# eksos-rj45-breakout16.net
KiCad netlist of a schematic drawn in EAGLE
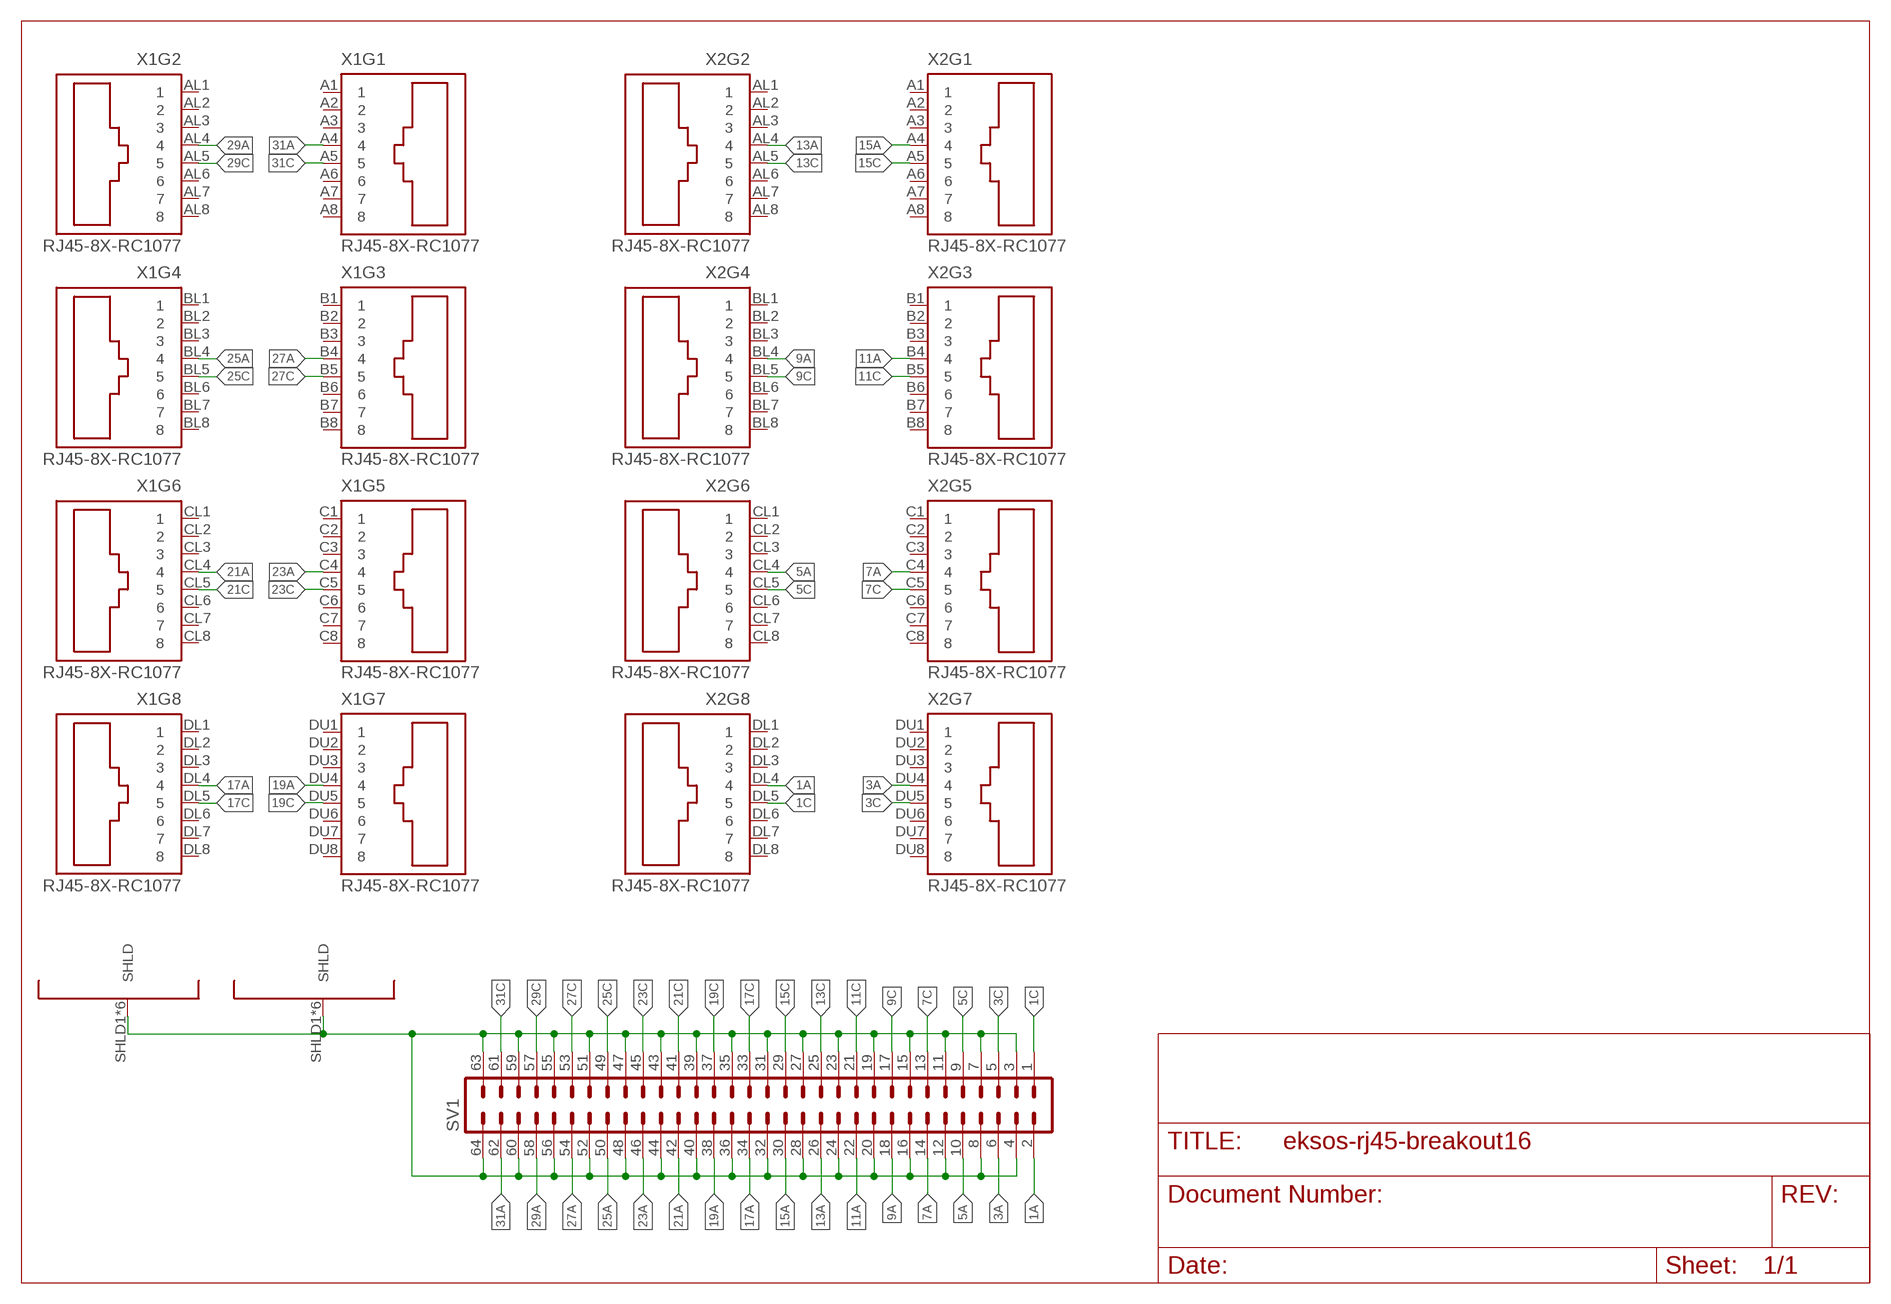
[diagram p0: schematic, sheet 1]

(export (version "E")
  (design (tool "Eeschema 10.0.6"))
  (components
    (comp (ref "SV1")
      (value "ML64")
      (footprint "eagle-import:ML64")
      (libsource (lib "eagle-import") (part "ML64"))
    )
    (comp (ref "X1")
      (value "RJ45-8X-RC1077")
      (footprint "eagle-import:RC01077")
      (libsource (lib "eagle-import") (part "RJ45-8X-RC1077"))
    )
    (comp (ref "X2")
      (value "RJ45-8X-RC1077")
      (footprint "eagle-import:RC01077")
      (libsource (lib "eagle-import") (part "RJ45-8X-RC1077"))
    )
  )
  (nets
    (net (code "1") (name "1A") (class "Default")
      (node (ref "SV1") (pin "2") (pinfunction "2_2") (pintype "passive"))
      (node (ref "X2") (pin "DL4") (pinfunction "4_DL4") (pintype "passive"))
    )
    (net (code "2") (name "1C") (class "Default")
      (node (ref "SV1") (pin "1") (pinfunction "1_1") (pintype "passive"))
      (node (ref "X2") (pin "DL5") (pinfunction "5_DL5") (pintype "passive"))
    )
    (net (code "3") (name "3A") (class "Default")
      (node (ref "SV1") (pin "6") (pinfunction "6_6") (pintype "passive"))
      (node (ref "X2") (pin "DU4") (pinfunction "4_DU4") (pintype "passive"))
    )
    (net (code "4") (name "3C") (class "Default")
      (node (ref "SV1") (pin "5") (pinfunction "5_5") (pintype "passive"))
      (node (ref "X2") (pin "DU5") (pinfunction "5_DU5") (pintype "passive"))
    )
    (net (code "5") (name "5A") (class "Default")
      (node (ref "SV1") (pin "10") (pinfunction "10_10") (pintype "passive"))
      (node (ref "X2") (pin "CL4") (pinfunction "4_CL4") (pintype "passive"))
    )
    (net (code "6") (name "5C") (class "Default")
      (node (ref "SV1") (pin "9") (pinfunction "9_9") (pintype "passive"))
      (node (ref "X2") (pin "CL5") (pinfunction "5_CL5") (pintype "passive"))
    )
    (net (code "7") (name "7A") (class "Default")
      (node (ref "SV1") (pin "14") (pinfunction "14_14") (pintype "passive"))
      (node (ref "X2") (pin "C4") (pinfunction "4_C4") (pintype "passive"))
    )
    (net (code "8") (name "7C") (class "Default")
      (node (ref "SV1") (pin "13") (pinfunction "13_13") (pintype "passive"))
      (node (ref "X2") (pin "C5") (pinfunction "5_C5") (pintype "passive"))
    )
    (net (code "9") (name "9A") (class "Default")
      (node (ref "SV1") (pin "18") (pinfunction "18_18") (pintype "passive"))
      (node (ref "X2") (pin "BL4") (pinfunction "4_BL4") (pintype "passive"))
    )
    (net (code "10") (name "9C") (class "Default")
      (node (ref "SV1") (pin "17") (pinfunction "17_17") (pintype "passive"))
      (node (ref "X2") (pin "BL5") (pinfunction "5_BL5") (pintype "passive"))
    )
    (net (code "11") (name "11A") (class "Default")
      (node (ref "SV1") (pin "22") (pinfunction "22_22") (pintype "passive"))
      (node (ref "X2") (pin "B4") (pinfunction "4_B4") (pintype "passive"))
    )
    (net (code "12") (name "11C") (class "Default")
      (node (ref "SV1") (pin "21") (pinfunction "21_21") (pintype "passive"))
      (node (ref "X2") (pin "B5") (pinfunction "5_B5") (pintype "passive"))
    )
    (net (code "13") (name "13A") (class "Default")
      (node (ref "SV1") (pin "26") (pinfunction "26_26") (pintype "passive"))
      (node (ref "X2") (pin "AL4") (pinfunction "4_AL4") (pintype "passive"))
    )
    (net (code "14") (name "13C") (class "Default")
      (node (ref "SV1") (pin "25") (pinfunction "25_25") (pintype "passive"))
      (node (ref "X2") (pin "AL5") (pinfunction "5_AL5") (pintype "passive"))
    )
    (net (code "15") (name "15A") (class "Default")
      (node (ref "SV1") (pin "30") (pinfunction "30_30") (pintype "passive"))
      (node (ref "X2") (pin "A4") (pinfunction "4_A4") (pintype "passive"))
    )
    (net (code "16") (name "15C") (class "Default")
      (node (ref "SV1") (pin "29") (pinfunction "29_29") (pintype "passive"))
      (node (ref "X2") (pin "A5") (pinfunction "5_A5") (pintype "passive"))
    )
    (net (code "17") (name "17A") (class "Default")
      (node (ref "SV1") (pin "34") (pinfunction "34_34") (pintype "passive"))
      (node (ref "X1") (pin "DL4") (pinfunction "4_DL4") (pintype "passive"))
    )
    (net (code "18") (name "17C") (class "Default")
      (node (ref "SV1") (pin "33") (pinfunction "33_33") (pintype "passive"))
      (node (ref "X1") (pin "DL5") (pinfunction "5_DL5") (pintype "passive"))
    )
    (net (code "19") (name "19A") (class "Default")
      (node (ref "SV1") (pin "38") (pinfunction "38_38") (pintype "passive"))
      (node (ref "X1") (pin "DU4") (pinfunction "4_DU4") (pintype "passive"))
    )
    (net (code "20") (name "19C") (class "Default")
      (node (ref "SV1") (pin "37") (pinfunction "37_37") (pintype "passive"))
      (node (ref "X1") (pin "DU5") (pinfunction "5_DU5") (pintype "passive"))
    )
    (net (code "21") (name "21A") (class "Default")
      (node (ref "SV1") (pin "42") (pinfunction "42_42") (pintype "passive"))
      (node (ref "X1") (pin "CL4") (pinfunction "4_CL4") (pintype "passive"))
    )
    (net (code "22") (name "21C") (class "Default")
      (node (ref "SV1") (pin "41") (pinfunction "41_41") (pintype "passive"))
      (node (ref "X1") (pin "CL5") (pinfunction "5_CL5") (pintype "passive"))
    )
    (net (code "23") (name "23A") (class "Default")
      (node (ref "SV1") (pin "46") (pinfunction "46_46") (pintype "passive"))
      (node (ref "X1") (pin "C4") (pinfunction "4_C4") (pintype "passive"))
    )
    (net (code "24") (name "23C") (class "Default")
      (node (ref "SV1") (pin "45") (pinfunction "45_45") (pintype "passive"))
      (node (ref "X1") (pin "C5") (pinfunction "5_C5") (pintype "passive"))
    )
    (net (code "25") (name "25A") (class "Default")
      (node (ref "SV1") (pin "50") (pinfunction "50_50") (pintype "passive"))
      (node (ref "X1") (pin "BL4") (pinfunction "4_BL4") (pintype "passive"))
    )
    (net (code "26") (name "25C") (class "Default")
      (node (ref "SV1") (pin "49") (pinfunction "49_49") (pintype "passive"))
      (node (ref "X1") (pin "BL5") (pinfunction "5_BL5") (pintype "passive"))
    )
    (net (code "27") (name "27A") (class "Default")
      (node (ref "SV1") (pin "54") (pinfunction "54_54") (pintype "passive"))
      (node (ref "X1") (pin "B4") (pinfunction "4_B4") (pintype "passive"))
    )
    (net (code "28") (name "27C") (class "Default")
      (node (ref "SV1") (pin "53") (pinfunction "53_53") (pintype "passive"))
      (node (ref "X1") (pin "B5") (pinfunction "5_B5") (pintype "passive"))
    )
    (net (code "29") (name "29A") (class "Default")
      (node (ref "SV1") (pin "58") (pinfunction "58_58") (pintype "passive"))
      (node (ref "X1") (pin "AL4") (pinfunction "4_AL4") (pintype "passive"))
    )
    (net (code "30") (name "29C") (class "Default")
      (node (ref "SV1") (pin "57") (pinfunction "57_57") (pintype "passive"))
      (node (ref "X1") (pin "AL5") (pinfunction "5_AL5") (pintype "passive"))
    )
    (net (code "31") (name "31A") (class "Default")
      (node (ref "SV1") (pin "62") (pinfunction "62_62") (pintype "passive"))
      (node (ref "X1") (pin "A4") (pinfunction "4_A4") (pintype "passive"))
    )
    (net (code "32") (name "31C") (class "Default")
      (node (ref "SV1") (pin "61") (pinfunction "61_61") (pintype "passive"))
      (node (ref "X1") (pin "A5") (pinfunction "5_A5") (pintype "passive"))
    )
    (net (code "33") (name "Net-(SV1-Pad11)") (class "Default")
      (node (ref "SV1") (pin "11") (pinfunction "11_11") (pintype "passive"))
      (node (ref "SV1") (pin "12") (pinfunction "12_12") (pintype "passive"))
      (node (ref "SV1") (pin "15") (pinfunction "15_15") (pintype "passive"))
      (node (ref "SV1") (pin "16") (pinfunction "16_16") (pintype "passive"))
      (node (ref "SV1") (pin "19") (pinfunction "19_19") (pintype "passive"))
      (node (ref "SV1") (pin "20") (pinfunction "20_20") (pintype "passive"))
      (node (ref "SV1") (pin "23") (pinfunction "23_23") (pintype "passive"))
      (node (ref "SV1") (pin "24") (pinfunction "24_24") (pintype "passive"))
      (node (ref "SV1") (pin "27") (pinfunction "27_27") (pintype "passive"))
      (node (ref "SV1") (pin "28") (pinfunction "28_28") (pintype "passive"))
      (node (ref "SV1") (pin "3") (pinfunction "3_3") (pintype "passive"))
      (node (ref "SV1") (pin "31") (pinfunction "31_31") (pintype "passive"))
      (node (ref "SV1") (pin "32") (pinfunction "32_32") (pintype "passive"))
      (node (ref "SV1") (pin "35") (pinfunction "35_35") (pintype "passive"))
      (node (ref "SV1") (pin "36") (pinfunction "36_36") (pintype "passive"))
      (node (ref "SV1") (pin "39") (pinfunction "39_39") (pintype "passive"))
      (node (ref "SV1") (pin "4") (pinfunction "4_4") (pintype "passive"))
      (node (ref "SV1") (pin "40") (pinfunction "40_40") (pintype "passive"))
      (node (ref "SV1") (pin "43") (pinfunction "43_43") (pintype "passive"))
      (node (ref "SV1") (pin "44") (pinfunction "44_44") (pintype "passive"))
      (node (ref "SV1") (pin "47") (pinfunction "47_47") (pintype "passive"))
      (node (ref "SV1") (pin "48") (pinfunction "48_48") (pintype "passive"))
      (node (ref "SV1") (pin "51") (pinfunction "51_51") (pintype "passive"))
      (node (ref "SV1") (pin "52") (pinfunction "52_52") (pintype "passive"))
      (node (ref "SV1") (pin "55") (pinfunction "55_55") (pintype "passive"))
      (node (ref "SV1") (pin "56") (pinfunction "56_56") (pintype "passive"))
      (node (ref "SV1") (pin "59") (pinfunction "59_59") (pintype "passive"))
      (node (ref "SV1") (pin "60") (pinfunction "60_60") (pintype "passive"))
      (node (ref "SV1") (pin "63") (pinfunction "63_63") (pintype "passive"))
      (node (ref "SV1") (pin "64") (pinfunction "64_64") (pintype "passive"))
      (node (ref "SV1") (pin "7") (pinfunction "7_7") (pintype "passive"))
      (node (ref "SV1") (pin "8") (pinfunction "8_8") (pintype "passive"))
      (node (ref "X1") (pin "SHLD1") (pinfunction "SHLD_SHLD1") (pintype "bidirectional"))
      (node (ref "X1") (pin "SHLD2") (pinfunction "SHLD_SHLD2") (pintype "bidirectional"))
      (node (ref "X1") (pin "SHLD3") (pinfunction "SHLD_SHLD3") (pintype "bidirectional"))
      (node (ref "X1") (pin "SHLD4") (pinfunction "SHLD_SHLD4") (pintype "bidirectional"))
      (node (ref "X1") (pin "SHLD5") (pinfunction "SHLD_SHLD5") (pintype "bidirectional"))
      (node (ref "X1") (pin "SHLD6") (pinfunction "SHLD_SHLD6") (pintype "bidirectional"))
      (node (ref "X2") (pin "SHLD1") (pinfunction "SHLD_SHLD1") (pintype "bidirectional"))
      (node (ref "X2") (pin "SHLD2") (pinfunction "SHLD_SHLD2") (pintype "bidirectional"))
      (node (ref "X2") (pin "SHLD3") (pinfunction "SHLD_SHLD3") (pintype "bidirectional"))
      (node (ref "X2") (pin "SHLD4") (pinfunction "SHLD_SHLD4") (pintype "bidirectional"))
      (node (ref "X2") (pin "SHLD5") (pinfunction "SHLD_SHLD5") (pintype "bidirectional"))
      (node (ref "X2") (pin "SHLD6") (pinfunction "SHLD_SHLD6") (pintype "bidirectional"))
    )
    (net (code "34") (name "unconnected-(X1B-1-PadA1)") (class "Default")
      (node (ref "X1") (pin "A1") (pinfunction "1_A1") (pintype "passive"))
    )
    (net (code "35") (name "unconnected-(X1B-2-PadA2)") (class "Default")
      (node (ref "X1") (pin "A2") (pinfunction "2_A2") (pintype "passive"))
    )
    (net (code "36") (name "unconnected-(X1B-3-PadA3)") (class "Default")
      (node (ref "X1") (pin "A3") (pinfunction "3_A3") (pintype "passive"))
    )
    (net (code "37") (name "unconnected-(X1B-6-PadA6)") (class "Default")
      (node (ref "X1") (pin "A6") (pinfunction "6_A6") (pintype "passive"))
    )
    (net (code "38") (name "unconnected-(X1B-7-PadA7)") (class "Default")
      (node (ref "X1") (pin "A7") (pinfunction "7_A7") (pintype "passive"))
    )
    (net (code "39") (name "unconnected-(X1B-8-PadA8)") (class "Default")
      (node (ref "X1") (pin "A8") (pinfunction "8_A8") (pintype "passive"))
    )
    (net (code "40") (name "unconnected-(X1C-1-PadAL1)") (class "Default")
      (node (ref "X1") (pin "AL1") (pinfunction "1_AL1") (pintype "passive"))
    )
    (net (code "41") (name "unconnected-(X1C-2-PadAL2)") (class "Default")
      (node (ref "X1") (pin "AL2") (pinfunction "2_AL2") (pintype "passive"))
    )
    (net (code "42") (name "unconnected-(X1C-3-PadAL3)") (class "Default")
      (node (ref "X1") (pin "AL3") (pinfunction "3_AL3") (pintype "passive"))
    )
    (net (code "43") (name "unconnected-(X1C-6-PadAL6)") (class "Default")
      (node (ref "X1") (pin "AL6") (pinfunction "6_AL6") (pintype "passive"))
    )
    (net (code "44") (name "unconnected-(X1C-7-PadAL7)") (class "Default")
      (node (ref "X1") (pin "AL7") (pinfunction "7_AL7") (pintype "passive"))
    )
    (net (code "45") (name "unconnected-(X1C-8-PadAL8)") (class "Default")
      (node (ref "X1") (pin "AL8") (pinfunction "8_AL8") (pintype "passive"))
    )
    (net (code "46") (name "unconnected-(X1D-1-PadB1)") (class "Default")
      (node (ref "X1") (pin "B1") (pinfunction "1_B1") (pintype "passive"))
    )
    (net (code "47") (name "unconnected-(X1D-2-PadB2)") (class "Default")
      (node (ref "X1") (pin "B2") (pinfunction "2_B2") (pintype "passive"))
    )
    (net (code "48") (name "unconnected-(X1D-3-PadB3)") (class "Default")
      (node (ref "X1") (pin "B3") (pinfunction "3_B3") (pintype "passive"))
    )
    (net (code "49") (name "unconnected-(X1D-6-PadB6)") (class "Default")
      (node (ref "X1") (pin "B6") (pinfunction "6_B6") (pintype "passive"))
    )
    (net (code "50") (name "unconnected-(X1D-7-PadB7)") (class "Default")
      (node (ref "X1") (pin "B7") (pinfunction "7_B7") (pintype "passive"))
    )
    (net (code "51") (name "unconnected-(X1D-8-PadB8)") (class "Default")
      (node (ref "X1") (pin "B8") (pinfunction "8_B8") (pintype "passive"))
    )
    (net (code "52") (name "unconnected-(X1E-1-PadBL1)") (class "Default")
      (node (ref "X1") (pin "BL1") (pinfunction "1_BL1") (pintype "passive"))
    )
    (net (code "53") (name "unconnected-(X1E-2-PadBL2)") (class "Default")
      (node (ref "X1") (pin "BL2") (pinfunction "2_BL2") (pintype "passive"))
    )
    (net (code "54") (name "unconnected-(X1E-3-PadBL3)") (class "Default")
      (node (ref "X1") (pin "BL3") (pinfunction "3_BL3") (pintype "passive"))
    )
    (net (code "55") (name "unconnected-(X1E-6-PadBL6)") (class "Default")
      (node (ref "X1") (pin "BL6") (pinfunction "6_BL6") (pintype "passive"))
    )
    (net (code "56") (name "unconnected-(X1E-7-PadBL7)") (class "Default")
      (node (ref "X1") (pin "BL7") (pinfunction "7_BL7") (pintype "passive"))
    )
    (net (code "57") (name "unconnected-(X1E-8-PadBL8)") (class "Default")
      (node (ref "X1") (pin "BL8") (pinfunction "8_BL8") (pintype "passive"))
    )
    (net (code "58") (name "unconnected-(X1F-1-PadC1)") (class "Default")
      (node (ref "X1") (pin "C1") (pinfunction "1_C1") (pintype "passive"))
    )
    (net (code "59") (name "unconnected-(X1F-2-PadC2)") (class "Default")
      (node (ref "X1") (pin "C2") (pinfunction "2_C2") (pintype "passive"))
    )
    (net (code "60") (name "unconnected-(X1F-3-PadC3)") (class "Default")
      (node (ref "X1") (pin "C3") (pinfunction "3_C3") (pintype "passive"))
    )
    (net (code "61") (name "unconnected-(X1F-6-PadC6)") (class "Default")
      (node (ref "X1") (pin "C6") (pinfunction "6_C6") (pintype "passive"))
    )
    (net (code "62") (name "unconnected-(X1F-7-PadC7)") (class "Default")
      (node (ref "X1") (pin "C7") (pinfunction "7_C7") (pintype "passive"))
    )
    (net (code "63") (name "unconnected-(X1F-8-PadC8)") (class "Default")
      (node (ref "X1") (pin "C8") (pinfunction "8_C8") (pintype "passive"))
    )
    (net (code "64") (name "unconnected-(X1G-1-PadCL1)") (class "Default")
      (node (ref "X1") (pin "CL1") (pinfunction "1_CL1") (pintype "passive"))
    )
    (net (code "65") (name "unconnected-(X1G-2-PadCL2)") (class "Default")
      (node (ref "X1") (pin "CL2") (pinfunction "2_CL2") (pintype "passive"))
    )
    (net (code "66") (name "unconnected-(X1G-3-PadCL3)") (class "Default")
      (node (ref "X1") (pin "CL3") (pinfunction "3_CL3") (pintype "passive"))
    )
    (net (code "67") (name "unconnected-(X1G-6-PadCL6)") (class "Default")
      (node (ref "X1") (pin "CL6") (pinfunction "6_CL6") (pintype "passive"))
    )
    (net (code "68") (name "unconnected-(X1G-7-PadCL7)") (class "Default")
      (node (ref "X1") (pin "CL7") (pinfunction "7_CL7") (pintype "passive"))
    )
    (net (code "69") (name "unconnected-(X1G-8-PadCL8)") (class "Default")
      (node (ref "X1") (pin "CL8") (pinfunction "8_CL8") (pintype "passive"))
    )
    (net (code "70") (name "unconnected-(X1H-1-PadDU1)") (class "Default")
      (node (ref "X1") (pin "DU1") (pinfunction "1_DU1") (pintype "passive"))
    )
    (net (code "71") (name "unconnected-(X1H-2-PadDU2)") (class "Default")
      (node (ref "X1") (pin "DU2") (pinfunction "2_DU2") (pintype "passive"))
    )
    (net (code "72") (name "unconnected-(X1H-3-PadDU3)") (class "Default")
      (node (ref "X1") (pin "DU3") (pinfunction "3_DU3") (pintype "passive"))
    )
    (net (code "73") (name "unconnected-(X1H-6-PadDU6)") (class "Default")
      (node (ref "X1") (pin "DU6") (pinfunction "6_DU6") (pintype "passive"))
    )
    (net (code "74") (name "unconnected-(X1H-7-PadDU7)") (class "Default")
      (node (ref "X1") (pin "DU7") (pinfunction "7_DU7") (pintype "passive"))
    )
    (net (code "75") (name "unconnected-(X1H-8-PadDU8)") (class "Default")
      (node (ref "X1") (pin "DU8") (pinfunction "8_DU8") (pintype "passive"))
    )
    (net (code "76") (name "unconnected-(X1I-1-PadDL1)") (class "Default")
      (node (ref "X1") (pin "DL1") (pinfunction "1_DL1") (pintype "passive"))
    )
    (net (code "77") (name "unconnected-(X1I-2-PadDL2)") (class "Default")
      (node (ref "X1") (pin "DL2") (pinfunction "2_DL2") (pintype "passive"))
    )
    (net (code "78") (name "unconnected-(X1I-3-PadDL3)") (class "Default")
      (node (ref "X1") (pin "DL3") (pinfunction "3_DL3") (pintype "passive"))
    )
    (net (code "79") (name "unconnected-(X1I-6-PadDL6)") (class "Default")
      (node (ref "X1") (pin "DL6") (pinfunction "6_DL6") (pintype "passive"))
    )
    (net (code "80") (name "unconnected-(X1I-7-PadDL7)") (class "Default")
      (node (ref "X1") (pin "DL7") (pinfunction "7_DL7") (pintype "passive"))
    )
    (net (code "81") (name "unconnected-(X1I-8-PadDL8)") (class "Default")
      (node (ref "X1") (pin "DL8") (pinfunction "8_DL8") (pintype "passive"))
    )
    (net (code "82") (name "unconnected-(X2B-1-PadA1)") (class "Default")
      (node (ref "X2") (pin "A1") (pinfunction "1_A1") (pintype "passive"))
    )
    (net (code "83") (name "unconnected-(X2B-2-PadA2)") (class "Default")
      (node (ref "X2") (pin "A2") (pinfunction "2_A2") (pintype "passive"))
    )
    (net (code "84") (name "unconnected-(X2B-3-PadA3)") (class "Default")
      (node (ref "X2") (pin "A3") (pinfunction "3_A3") (pintype "passive"))
    )
    (net (code "85") (name "unconnected-(X2B-6-PadA6)") (class "Default")
      (node (ref "X2") (pin "A6") (pinfunction "6_A6") (pintype "passive"))
    )
    (net (code "86") (name "unconnected-(X2B-7-PadA7)") (class "Default")
      (node (ref "X2") (pin "A7") (pinfunction "7_A7") (pintype "passive"))
    )
    (net (code "87") (name "unconnected-(X2B-8-PadA8)") (class "Default")
      (node (ref "X2") (pin "A8") (pinfunction "8_A8") (pintype "passive"))
    )
    (net (code "88") (name "unconnected-(X2C-1-PadAL1)") (class "Default")
      (node (ref "X2") (pin "AL1") (pinfunction "1_AL1") (pintype "passive"))
    )
    (net (code "89") (name "unconnected-(X2C-2-PadAL2)") (class "Default")
      (node (ref "X2") (pin "AL2") (pinfunction "2_AL2") (pintype "passive"))
    )
    (net (code "90") (name "unconnected-(X2C-3-PadAL3)") (class "Default")
      (node (ref "X2") (pin "AL3") (pinfunction "3_AL3") (pintype "passive"))
    )
    (net (code "91") (name "unconnected-(X2C-6-PadAL6)") (class "Default")
      (node (ref "X2") (pin "AL6") (pinfunction "6_AL6") (pintype "passive"))
    )
    (net (code "92") (name "unconnected-(X2C-7-PadAL7)") (class "Default")
      (node (ref "X2") (pin "AL7") (pinfunction "7_AL7") (pintype "passive"))
    )
    (net (code "93") (name "unconnected-(X2C-8-PadAL8)") (class "Default")
      (node (ref "X2") (pin "AL8") (pinfunction "8_AL8") (pintype "passive"))
    )
    (net (code "94") (name "unconnected-(X2D-1-PadB1)") (class "Default")
      (node (ref "X2") (pin "B1") (pinfunction "1_B1") (pintype "passive"))
    )
    (net (code "95") (name "unconnected-(X2D-2-PadB2)") (class "Default")
      (node (ref "X2") (pin "B2") (pinfunction "2_B2") (pintype "passive"))
    )
    (net (code "96") (name "unconnected-(X2D-3-PadB3)") (class "Default")
      (node (ref "X2") (pin "B3") (pinfunction "3_B3") (pintype "passive"))
    )
    (net (code "97") (name "unconnected-(X2D-6-PadB6)") (class "Default")
      (node (ref "X2") (pin "B6") (pinfunction "6_B6") (pintype "passive"))
    )
    (net (code "98") (name "unconnected-(X2D-7-PadB7)") (class "Default")
      (node (ref "X2") (pin "B7") (pinfunction "7_B7") (pintype "passive"))
    )
    (net (code "99") (name "unconnected-(X2D-8-PadB8)") (class "Default")
      (node (ref "X2") (pin "B8") (pinfunction "8_B8") (pintype "passive"))
    )
    (net (code "100") (name "unconnected-(X2E-1-PadBL1)") (class "Default")
      (node (ref "X2") (pin "BL1") (pinfunction "1_BL1") (pintype "passive"))
    )
    (net (code "101") (name "unconnected-(X2E-2-PadBL2)") (class "Default")
      (node (ref "X2") (pin "BL2") (pinfunction "2_BL2") (pintype "passive"))
    )
    (net (code "102") (name "unconnected-(X2E-3-PadBL3)") (class "Default")
      (node (ref "X2") (pin "BL3") (pinfunction "3_BL3") (pintype "passive"))
    )
    (net (code "103") (name "unconnected-(X2E-6-PadBL6)") (class "Default")
      (node (ref "X2") (pin "BL6") (pinfunction "6_BL6") (pintype "passive"))
    )
    (net (code "104") (name "unconnected-(X2E-7-PadBL7)") (class "Default")
      (node (ref "X2") (pin "BL7") (pinfunction "7_BL7") (pintype "passive"))
    )
    (net (code "105") (name "unconnected-(X2E-8-PadBL8)") (class "Default")
      (node (ref "X2") (pin "BL8") (pinfunction "8_BL8") (pintype "passive"))
    )
    (net (code "106") (name "unconnected-(X2F-1-PadC1)") (class "Default")
      (node (ref "X2") (pin "C1") (pinfunction "1_C1") (pintype "passive"))
    )
    (net (code "107") (name "unconnected-(X2F-2-PadC2)") (class "Default")
      (node (ref "X2") (pin "C2") (pinfunction "2_C2") (pintype "passive"))
    )
    (net (code "108") (name "unconnected-(X2F-3-PadC3)") (class "Default")
      (node (ref "X2") (pin "C3") (pinfunction "3_C3") (pintype "passive"))
    )
    (net (code "109") (name "unconnected-(X2F-6-PadC6)") (class "Default")
      (node (ref "X2") (pin "C6") (pinfunction "6_C6") (pintype "passive"))
    )
    (net (code "110") (name "unconnected-(X2F-7-PadC7)") (class "Default")
      (node (ref "X2") (pin "C7") (pinfunction "7_C7") (pintype "passive"))
    )
    (net (code "111") (name "unconnected-(X2F-8-PadC8)") (class "Default")
      (node (ref "X2") (pin "C8") (pinfunction "8_C8") (pintype "passive"))
    )
    (net (code "112") (name "unconnected-(X2G-1-PadCL1)") (class "Default")
      (node (ref "X2") (pin "CL1") (pinfunction "1_CL1") (pintype "passive"))
    )
    (net (code "113") (name "unconnected-(X2G-2-PadCL2)") (class "Default")
      (node (ref "X2") (pin "CL2") (pinfunction "2_CL2") (pintype "passive"))
    )
    (net (code "114") (name "unconnected-(X2G-3-PadCL3)") (class "Default")
      (node (ref "X2") (pin "CL3") (pinfunction "3_CL3") (pintype "passive"))
    )
    (net (code "115") (name "unconnected-(X2G-6-PadCL6)") (class "Default")
      (node (ref "X2") (pin "CL6") (pinfunction "6_CL6") (pintype "passive"))
    )
    (net (code "116") (name "unconnected-(X2G-7-PadCL7)") (class "Default")
      (node (ref "X2") (pin "CL7") (pinfunction "7_CL7") (pintype "passive"))
    )
    (net (code "117") (name "unconnected-(X2G-8-PadCL8)") (class "Default")
      (node (ref "X2") (pin "CL8") (pinfunction "8_CL8") (pintype "passive"))
    )
    (net (code "118") (name "unconnected-(X2H-1-PadDU1)") (class "Default")
      (node (ref "X2") (pin "DU1") (pinfunction "1_DU1") (pintype "passive"))
    )
    (net (code "119") (name "unconnected-(X2H-2-PadDU2)") (class "Default")
      (node (ref "X2") (pin "DU2") (pinfunction "2_DU2") (pintype "passive"))
    )
    (net (code "120") (name "unconnected-(X2H-3-PadDU3)") (class "Default")
      (node (ref "X2") (pin "DU3") (pinfunction "3_DU3") (pintype "passive"))
    )
    (net (code "121") (name "unconnected-(X2H-6-PadDU6)") (class "Default")
      (node (ref "X2") (pin "DU6") (pinfunction "6_DU6") (pintype "passive"))
    )
    (net (code "122") (name "unconnected-(X2H-7-PadDU7)") (class "Default")
      (node (ref "X2") (pin "DU7") (pinfunction "7_DU7") (pintype "passive"))
    )
    (net (code "123") (name "unconnected-(X2H-8-PadDU8)") (class "Default")
      (node (ref "X2") (pin "DU8") (pinfunction "8_DU8") (pintype "passive"))
    )
    (net (code "124") (name "unconnected-(X2I-1-PadDL1)") (class "Default")
      (node (ref "X2") (pin "DL1") (pinfunction "1_DL1") (pintype "passive"))
    )
    (net (code "125") (name "unconnected-(X2I-2-PadDL2)") (class "Default")
      (node (ref "X2") (pin "DL2") (pinfunction "2_DL2") (pintype "passive"))
    )
    (net (code "126") (name "unconnected-(X2I-3-PadDL3)") (class "Default")
      (node (ref "X2") (pin "DL3") (pinfunction "3_DL3") (pintype "passive"))
    )
    (net (code "127") (name "unconnected-(X2I-6-PadDL6)") (class "Default")
      (node (ref "X2") (pin "DL6") (pinfunction "6_DL6") (pintype "passive"))
    )
    (net (code "128") (name "unconnected-(X2I-7-PadDL7)") (class "Default")
      (node (ref "X2") (pin "DL7") (pinfunction "7_DL7") (pintype "passive"))
    )
    (net (code "129") (name "unconnected-(X2I-8-PadDL8)") (class "Default")
      (node (ref "X2") (pin "DL8") (pinfunction "8_DL8") (pintype "passive"))
    )
  )
)
